# Adafruit_SMT_Datalogger_Shield.net
KiCad netlist of a schematic drawn in EAGLE
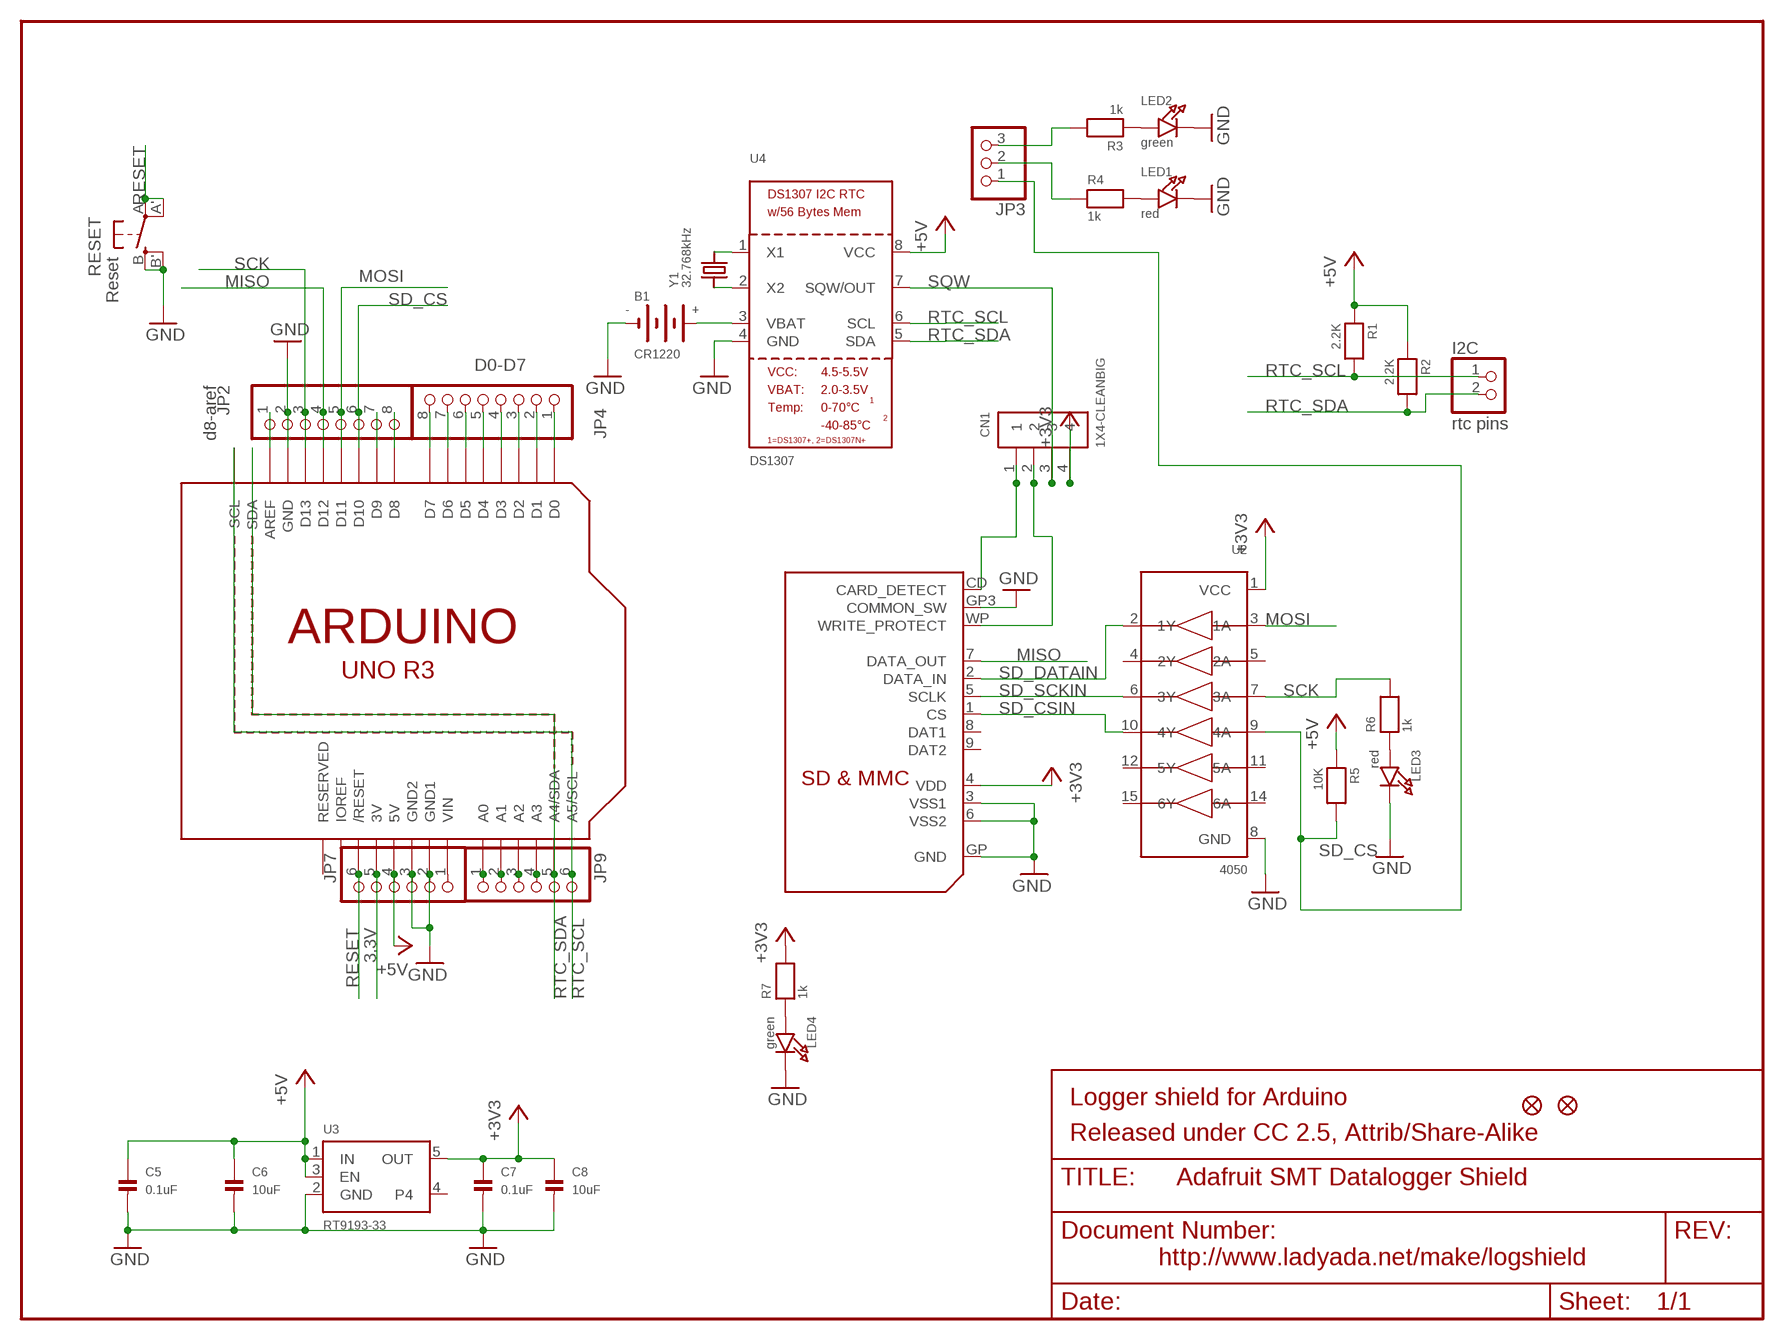
[diagram p0: schematic, sheet 1]

(export (version "E")
  (design (tool "Eeschema 10.0.6"))
  (components
    (comp (ref "B1")
      (value "CR1220")
      (footprint "eagle-import:CR1220")
      (libsource (lib "eagle-import") (part "BATTERYCR1220_SMT"))
    )
    (comp (ref "C5")
      (value "0.1uF")
      (footprint "eagle-import:0805")
      (libsource (lib "eagle-import") (part "CAP_CERAMIC0805"))
    )
    (comp (ref "C6")
      (value "10uF")
      (footprint "eagle-import:0805")
      (libsource (lib "eagle-import") (part "CAP_CERAMIC0805"))
    )
    (comp (ref "C7")
      (value "0.1uF")
      (footprint "eagle-import:0805")
      (libsource (lib "eagle-import") (part "CAP_CERAMIC0805"))
    )
    (comp (ref "C8")
      (value "10uF")
      (footprint "eagle-import:0805")
      (libsource (lib "eagle-import") (part "CAP_CERAMIC0805"))
    )
    (comp (ref "CN1")
      (value "1X4-CLEANBIG")
      (footprint "eagle-import:1X04-CLEANBIG")
      (libsource (lib "eagle-import") (part "1X4-CLEANBIG"))
    )
    (comp (ref "FID1")
      (value "FIDUCIAL1X2.5")
      (footprint "eagle-import:FIDUCIAL-1X2.5")
      (libsource (lib "eagle-import") (part "FIDUCIAL1X2.5"))
    )
    (comp (ref "FID3")
      (value "FIDUCIAL1X2.5")
      (footprint "eagle-import:FIDUCIAL-1X2.5")
      (libsource (lib "eagle-import") (part "FIDUCIAL1X2.5"))
    )
    (comp (ref "I2C")
      (value "rtc pins")
      (footprint "eagle-import:1X02")
      (libsource (lib "eagle-import") (part "PINHD-1X2"))
    )
    (comp (ref "JP2")
      (value "d8-aref")
      (footprint "eagle-import:1X08-BIG")
      (libsource (lib "eagle-import") (part "PINHD-1X8BIG"))
    )
    (comp (ref "JP3")
      (value "HEADER-1X3ROUND")
      (footprint "eagle-import:1X03_ROUND")
      (libsource (lib "eagle-import") (part "HEADER-1X3ROUND"))
    )
    (comp (ref "JP4")
      (value "D0-D7")
      (footprint "eagle-import:1X08-BIG")
      (libsource (lib "eagle-import") (part "PINHD-1X8BIG"))
    )
    (comp (ref "JP7")
      (value "PINHD-1X6B")
      (footprint "eagle-import:1X06-BIG")
      (libsource (lib "eagle-import") (part "PINHD-1X6B"))
    )
    (comp (ref "JP9")
      (value "PINHD-1X6B")
      (footprint "eagle-import:1X06-BIG")
      (libsource (lib "eagle-import") (part "PINHD-1X6B"))
    )
    (comp (ref "LED1")
      (value "red")
      (footprint "eagle-import:CHIPLED_0805")
      (libsource (lib "eagle-import") (part "LED0805"))
    )
    (comp (ref "LED2")
      (value "green")
      (footprint "eagle-import:CHIPLED_0805")
      (libsource (lib "eagle-import") (part "LED0805"))
    )
    (comp (ref "LED3")
      (value "red")
      (footprint "eagle-import:CHIPLED_0805")
      (libsource (lib "eagle-import") (part "LED0805"))
    )
    (comp (ref "LED4")
      (value "green")
      (footprint "eagle-import:CHIPLED_0805")
      (libsource (lib "eagle-import") (part "LED0805"))
    )
    (comp (ref "R1")
      (value "2.2K")
      (footprint "eagle-import:0805")
      (libsource (lib "eagle-import") (part "RESISTOR0805"))
    )
    (comp (ref "R2")
      (value "2.2K")
      (footprint "eagle-import:0805")
      (libsource (lib "eagle-import") (part "RESISTOR0805"))
    )
    (comp (ref "R3")
      (value "1k")
      (footprint "eagle-import:0805")
      (libsource (lib "eagle-import") (part "RESISTOR0805"))
    )
    (comp (ref "R4")
      (value "1k")
      (footprint "eagle-import:0805")
      (libsource (lib "eagle-import") (part "RESISTOR0805"))
    )
    (comp (ref "R5")
      (value "10K")
      (footprint "eagle-import:0805")
      (libsource (lib "eagle-import") (part "RESISTOR0805"))
    )
    (comp (ref "R6")
      (value "1k")
      (footprint "eagle-import:0805")
      (libsource (lib "eagle-import") (part "RESISTOR0805"))
    )
    (comp (ref "R7")
      (value "1k")
      (footprint "eagle-import:0805")
      (libsource (lib "eagle-import") (part "RESISTOR0805"))
    )
    (comp (ref "RESET")
      (value "Reset")
      (footprint "eagle-import:EVQ-Q2")
      (libsource (lib "eagle-import") (part "SPST_TACT-EVQQ2"))
    )
    (comp (ref "U$2")
      (value "SDMMC06132")
      (footprint "eagle-import:06132")
      (libsource (lib "eagle-import") (part "SDMMC06132"))
    )
    (comp (ref "U1")
      (value "ARDUINOR3-DIMENSION")
      (footprint "eagle-import:ARDUINOR3")
      (libsource (lib "eagle-import") (part "ARDUINOR3-DIMENSION"))
    )
    (comp (ref "U2")
      (value "4050")
      (footprint "eagle-import:SOIC16")
      (libsource (lib "eagle-import") (part "74HC4050D"))
    )
    (comp (ref "U3")
      (value "RT9193-33")
      (footprint "eagle-import:SOT23-5")
      (libsource (lib "eagle-import") (part "VREG_SOT23-5"))
    )
    (comp (ref "U4")
      (value "DS1307")
      (footprint "eagle-import:SOIC8_150MIL")
      (libsource (lib "eagle-import") (part "RTC_DS1307"))
    )
    (comp (ref "Y1")
      (value "32.768kHz")
      (footprint "eagle-import:CRYSTAL_8X3.8")
      (libsource (lib "eagle-import") (part "CRYSTAL8X3.8SMT"))
    )
  )
  (nets
    (net (code "1") (name "+3V3") (class "Default")
      (node (ref "C7") (pin "1") (pinfunction "P$1_1") (pintype "passive"))
      (node (ref "C8") (pin "1") (pinfunction "P$1_1") (pintype "passive"))
      (node (ref "CN1") (pin "4") (pinfunction "4_4") (pintype "bidirectional"))
      (node (ref "R7") (pin "2") (pinfunction "2_2") (pintype "passive"))
      (node (ref "U$2") (pin "4") (pinfunction "VDD_4") (pintype "power_in"))
      (node (ref "U2") (pin "1") (pinfunction "VCC_1") (pintype "bidirectional"))
      (node (ref "U3") (pin "5") (pinfunction "OUT_5") (pintype "bidirectional"))
    )
    (net (code "2") (name "+5V") (class "Default")
      (node (ref "C5") (pin "1") (pinfunction "P$1_1") (pintype "passive"))
      (node (ref "C6") (pin "1") (pinfunction "P$1_1") (pintype "passive"))
      (node (ref "JP7") (pin "4") (pinfunction "4_4") (pintype "passive"))
      (node (ref "R1") (pin "1") (pinfunction "1_1") (pintype "passive"))
      (node (ref "R2") (pin "1") (pinfunction "1_1") (pintype "passive"))
      (node (ref "R5") (pin "1") (pinfunction "1_1") (pintype "passive"))
      (node (ref "U1") (pin "5V") (pinfunction "5V_5V") (pintype "power_in"))
      (node (ref "U3") (pin "1") (pinfunction "IN_1") (pintype "bidirectional"))
      (node (ref "U3") (pin "3") (pinfunction "EN_3") (pintype "bidirectional"))
      (node (ref "U4") (pin "8") (pinfunction "VCC_8") (pintype "bidirectional"))
    )
    (net (code "3") (name "/3.3V") (class "Default")
      (node (ref "JP7") (pin "5") (pinfunction "5_5") (pintype "passive"))
      (node (ref "U1") (pin "3V") (pinfunction "3V_3V") (pintype "power_in"))
    )
    (net (code "4") (name "/MISO") (class "Default")
      (node (ref "JP2") (pin "4") (pinfunction "4_4") (pintype "passive"))
      (node (ref "U$2") (pin "7") (pinfunction "DATA_OUT_7") (pintype "output"))
      (node (ref "U1") (pin "D12") (pinfunction "D12_D12") (pintype "bidirectional"))
    )
    (net (code "5") (name "/MOSI") (class "Default")
      (node (ref "JP2") (pin "5") (pinfunction "5_5") (pintype "passive"))
      (node (ref "U1") (pin "D11") (pinfunction "D11_D11") (pintype "bidirectional"))
      (node (ref "U2") (pin "3") (pinfunction "1A_3") (pintype "bidirectional"))
    )
    (net (code "6") (name "/RESET") (class "Default")
      (node (ref "JP7") (pin "6") (pinfunction "6_6") (pintype "passive"))
      (node (ref "RESET") (pin "A") (pinfunction "P_A") (pintype "passive"))
      (node (ref "RESET") (pin "A'") (pinfunction "P1_A'") (pintype "passive"))
      (node (ref "U1") (pin "RESET") (pinfunction "/RESET_RESET") (pintype "bidirectional"))
    )
    (net (code "7") (name "/RTC_SCL") (class "Default")
      (node (ref "I2C") (pin "1") (pinfunction "1_1") (pintype "passive"))
      (node (ref "JP9") (pin "6") (pinfunction "6_6") (pintype "passive"))
      (node (ref "R1") (pin "2") (pinfunction "2_2") (pintype "passive"))
      (node (ref "U1") (pin "A5") (pinfunction "A5/SCL_A5") (pintype "bidirectional"))
      (node (ref "U1") (pin "SCL") (pinfunction "SCL_SCL") (pintype "bidirectional"))
      (node (ref "U4") (pin "6") (pinfunction "SCL_6") (pintype "bidirectional"))
    )
    (net (code "8") (name "/RTC_SDA") (class "Default")
      (node (ref "I2C") (pin "2") (pinfunction "2_2") (pintype "passive"))
      (node (ref "JP9") (pin "5") (pinfunction "5_5") (pintype "passive"))
      (node (ref "R2") (pin "2") (pinfunction "2_2") (pintype "passive"))
      (node (ref "U1") (pin "A4") (pinfunction "A4/SDA_A4") (pintype "bidirectional"))
      (node (ref "U1") (pin "SDA") (pinfunction "SDA_SDA") (pintype "bidirectional"))
      (node (ref "U4") (pin "5") (pinfunction "SDA_5") (pintype "bidirectional"))
    )
    (net (code "9") (name "/SCK") (class "Default")
      (node (ref "JP2") (pin "3") (pinfunction "3_3") (pintype "passive"))
      (node (ref "R6") (pin "2") (pinfunction "2_2") (pintype "passive"))
      (node (ref "U1") (pin "D13") (pinfunction "D13_D13") (pintype "bidirectional"))
      (node (ref "U2") (pin "7") (pinfunction "3A_7") (pintype "bidirectional"))
    )
    (net (code "10") (name "/SD_CS") (class "Default")
      (node (ref "JP2") (pin "6") (pinfunction "6_6") (pintype "passive"))
      (node (ref "JP3") (pin "1") (pinfunction "1_1") (pintype "passive"))
      (node (ref "R5") (pin "2") (pinfunction "2_2") (pintype "passive"))
      (node (ref "U1") (pin "D10") (pinfunction "D10_D10") (pintype "bidirectional"))
      (node (ref "U2") (pin "9") (pinfunction "4A_9") (pintype "bidirectional"))
    )
    (net (code "11") (name "/SD_CSIN") (class "Default")
      (node (ref "U$2") (pin "1") (pinfunction "CS_1") (pintype "input"))
      (node (ref "U2") (pin "10") (pinfunction "4Y_10") (pintype "bidirectional"))
    )
    (net (code "12") (name "/SD_DATAIN") (class "Default")
      (node (ref "U$2") (pin "2") (pinfunction "DATA_IN_2") (pintype "input"))
      (node (ref "U2") (pin "2") (pinfunction "1Y_2") (pintype "bidirectional"))
    )
    (net (code "13") (name "/SD_SCKIN") (class "Default")
      (node (ref "U$2") (pin "5") (pinfunction "SCLK_5") (pintype "input"))
      (node (ref "U2") (pin "6") (pinfunction "3Y_6") (pintype "bidirectional"))
    )
    (net (code "14") (name "/SQW") (class "Default")
      (node (ref "CN1") (pin "3") (pinfunction "3_3") (pintype "bidirectional"))
      (node (ref "U4") (pin "7") (pinfunction "SQW/OUT_7") (pintype "bidirectional"))
    )
    (net (code "15") (name "GND") (class "Default")
      (node (ref "B1") (pin "-") (pinfunction "-_-") (pintype "passive"))
      (node (ref "C5") (pin "2") (pinfunction "P$2_2") (pintype "passive"))
      (node (ref "C6") (pin "2") (pinfunction "P$2_2") (pintype "passive"))
      (node (ref "C7") (pin "2") (pinfunction "P$2_2") (pintype "passive"))
      (node (ref "C8") (pin "2") (pinfunction "P$2_2") (pintype "passive"))
      (node (ref "JP2") (pin "2") (pinfunction "2_2") (pintype "passive"))
      (node (ref "JP7") (pin "2") (pinfunction "2_2") (pintype "passive"))
      (node (ref "JP7") (pin "3") (pinfunction "3_3") (pintype "passive"))
      (node (ref "LED1") (pin "C") (pinfunction "C_C") (pintype "passive"))
      (node (ref "LED2") (pin "C") (pinfunction "C_C") (pintype "passive"))
      (node (ref "LED3") (pin "C") (pinfunction "C_C") (pintype "passive"))
      (node (ref "LED4") (pin "C") (pinfunction "C_C") (pintype "passive"))
      (node (ref "RESET") (pin "B") (pinfunction "S_B") (pintype "passive"))
      (node (ref "RESET") (pin "B'") (pinfunction "S1_B'") (pintype "passive"))
      (node (ref "U$2") (pin "3") (pinfunction "VSS1_3") (pintype "power_in"))
      (node (ref "U$2") (pin "6") (pinfunction "VSS2_6") (pintype "power_in"))
      (node (ref "U$2") (pin "GP") (pinfunction "GND_GP") (pintype "power_in"))
      (node (ref "U$2") (pin "GP3") (pinfunction "COMMON_SW_GP3") (pintype "passive"))
      (node (ref "U1") (pin "GND") (pinfunction "GND_GND") (pintype "power_in"))
      (node (ref "U1") (pin "GND1") (pinfunction "GND1_GND1") (pintype "power_in"))
      (node (ref "U1") (pin "GND2") (pinfunction "GND2_GND2") (pintype "power_in"))
      (node (ref "U2") (pin "8") (pinfunction "GND_8") (pintype "bidirectional"))
      (node (ref "U3") (pin "2") (pinfunction "GND_2") (pintype "bidirectional"))
      (node (ref "U4") (pin "4") (pinfunction "GND_4") (pintype "bidirectional"))
    )
    (net (code "16") (name "Net-(B1-+)") (class "Default")
      (node (ref "B1") (pin "+$1") (pinfunction "+_+$1") (pintype "passive"))
      (node (ref "U4") (pin "3") (pinfunction "VBAT_3") (pintype "bidirectional"))
    )
    (net (code "17") (name "Net-(JP2-Pad1)") (class "Default")
      (node (ref "JP2") (pin "1") (pinfunction "1_1") (pintype "passive"))
      (node (ref "U1") (pin "AREF") (pinfunction "AREF_AREF") (pintype "bidirectional"))
    )
    (net (code "18") (name "Net-(JP2-Pad7)") (class "Default")
      (node (ref "JP2") (pin "7") (pinfunction "7_7") (pintype "passive"))
      (node (ref "U1") (pin "D9") (pinfunction "D9_D9") (pintype "bidirectional"))
    )
    (net (code "19") (name "Net-(JP2-Pad8)") (class "Default")
      (node (ref "JP2") (pin "8") (pinfunction "8_8") (pintype "passive"))
      (node (ref "U1") (pin "D8") (pinfunction "D8_D8") (pintype "bidirectional"))
    )
    (net (code "20") (name "Net-(JP3-Pad2)") (class "Default")
      (node (ref "JP3") (pin "2") (pinfunction "2_2") (pintype "passive"))
      (node (ref "R4") (pin "1") (pinfunction "1_1") (pintype "passive"))
    )
    (net (code "21") (name "Net-(JP3-Pad3)") (class "Default")
      (node (ref "JP3") (pin "3") (pinfunction "3_3") (pintype "passive"))
      (node (ref "R3") (pin "2") (pinfunction "2_2") (pintype "passive"))
    )
    (net (code "22") (name "Net-(JP4-Pad1)") (class "Default")
      (node (ref "JP4") (pin "1") (pinfunction "1_1") (pintype "passive"))
      (node (ref "U1") (pin "D0") (pinfunction "D0_D0") (pintype "bidirectional"))
    )
    (net (code "23") (name "Net-(JP4-Pad2)") (class "Default")
      (node (ref "JP4") (pin "2") (pinfunction "2_2") (pintype "passive"))
      (node (ref "U1") (pin "D1") (pinfunction "D1_D1") (pintype "bidirectional"))
    )
    (net (code "24") (name "Net-(JP4-Pad3)") (class "Default")
      (node (ref "JP4") (pin "3") (pinfunction "3_3") (pintype "passive"))
      (node (ref "U1") (pin "D2") (pinfunction "D2_D2") (pintype "bidirectional"))
    )
    (net (code "25") (name "Net-(JP4-Pad4)") (class "Default")
      (node (ref "JP4") (pin "4") (pinfunction "4_4") (pintype "passive"))
      (node (ref "U1") (pin "D3") (pinfunction "D3_D3") (pintype "bidirectional"))
    )
    (net (code "26") (name "Net-(JP4-Pad5)") (class "Default")
      (node (ref "JP4") (pin "5") (pinfunction "5_5") (pintype "passive"))
      (node (ref "U1") (pin "D4") (pinfunction "D4_D4") (pintype "bidirectional"))
    )
    (net (code "27") (name "Net-(JP4-Pad6)") (class "Default")
      (node (ref "JP4") (pin "6") (pinfunction "6_6") (pintype "passive"))
      (node (ref "U1") (pin "D5") (pinfunction "D5_D5") (pintype "bidirectional"))
    )
    (net (code "28") (name "Net-(JP4-Pad7)") (class "Default")
      (node (ref "JP4") (pin "7") (pinfunction "7_7") (pintype "passive"))
      (node (ref "U1") (pin "D6") (pinfunction "D6_D6") (pintype "bidirectional"))
    )
    (net (code "29") (name "Net-(JP4-Pad8)") (class "Default")
      (node (ref "JP4") (pin "8") (pinfunction "8_8") (pintype "passive"))
      (node (ref "U1") (pin "D7") (pinfunction "D7_D7") (pintype "bidirectional"))
    )
    (net (code "30") (name "Net-(JP7-Pad1)") (class "Default")
      (node (ref "JP7") (pin "1") (pinfunction "1_1") (pintype "passive"))
      (node (ref "U1") (pin "VIN") (pinfunction "VIN_VIN") (pintype "power_in"))
    )
    (net (code "31") (name "Net-(JP9-Pad1)") (class "Default")
      (node (ref "JP9") (pin "1") (pinfunction "1_1") (pintype "passive"))
      (node (ref "U1") (pin "A0") (pinfunction "A0_A0") (pintype "bidirectional"))
    )
    (net (code "32") (name "Net-(JP9-Pad2)") (class "Default")
      (node (ref "JP9") (pin "2") (pinfunction "2_2") (pintype "passive"))
      (node (ref "U1") (pin "A1") (pinfunction "A1_A1") (pintype "bidirectional"))
    )
    (net (code "33") (name "Net-(JP9-Pad3)") (class "Default")
      (node (ref "JP9") (pin "3") (pinfunction "3_3") (pintype "passive"))
      (node (ref "U1") (pin "A2") (pinfunction "A2_A2") (pintype "bidirectional"))
    )
    (net (code "34") (name "Net-(JP9-Pad4)") (class "Default")
      (node (ref "JP9") (pin "4") (pinfunction "4_4") (pintype "passive"))
      (node (ref "U1") (pin "A3") (pinfunction "A3_A3") (pintype "bidirectional"))
    )
    (net (code "35") (name "Net-(LED1-PadA)") (class "Default")
      (node (ref "LED1") (pin "A") (pinfunction "A_A") (pintype "passive"))
      (node (ref "R4") (pin "2") (pinfunction "2_2") (pintype "passive"))
    )
    (net (code "36") (name "Net-(LED2-PadA)") (class "Default")
      (node (ref "LED2") (pin "A") (pinfunction "A_A") (pintype "passive"))
      (node (ref "R3") (pin "1") (pinfunction "1_1") (pintype "passive"))
    )
    (net (code "37") (name "Net-(LED3-PadA)") (class "Default")
      (node (ref "LED3") (pin "A") (pinfunction "A_A") (pintype "passive"))
      (node (ref "R6") (pin "1") (pinfunction "1_1") (pintype "passive"))
    )
    (net (code "38") (name "Net-(LED4-PadA)") (class "Default")
      (node (ref "LED4") (pin "A") (pinfunction "A_A") (pintype "passive"))
      (node (ref "R7") (pin "1") (pinfunction "1_1") (pintype "passive"))
    )
    (net (code "39") (name "Net-(U$2-CARD_DETECT)") (class "Default")
      (node (ref "CN1") (pin "1") (pinfunction "1_1") (pintype "bidirectional"))
      (node (ref "U$2") (pin "CD") (pinfunction "CARD_DETECT_CD") (pintype "passive"))
    )
    (net (code "40") (name "Net-(U$2-WRITE_PROTECT)") (class "Default")
      (node (ref "CN1") (pin "2") (pinfunction "2_2") (pintype "bidirectional"))
      (node (ref "U$2") (pin "WP") (pinfunction "WRITE_PROTECT_WP") (pintype "passive"))
    )
    (net (code "41") (name "Net-(U4-X1)") (class "Default")
      (node (ref "U4") (pin "1") (pinfunction "X1_1") (pintype "bidirectional"))
      (node (ref "Y1") (pin "P$4") (pinfunction "2_P$4") (pintype "passive"))
    )
    (net (code "42") (name "Net-(U4-X2)") (class "Default")
      (node (ref "U4") (pin "2") (pinfunction "X2_2") (pintype "bidirectional"))
      (node (ref "Y1") (pin "P$1") (pinfunction "1_P$1") (pintype "passive"))
    )
    (net (code "43") (name "unconnected-(U$2-DAT1-Pad8)") (class "Default")
      (node (ref "U$2") (pin "8") (pinfunction "DAT1_8") (pintype "bidirectional"))
    )
    (net (code "44") (name "unconnected-(U$2-DAT2-Pad9)") (class "Default")
      (node (ref "U$2") (pin "9") (pinfunction "DAT2_9") (pintype "bidirectional"))
    )
    (net (code "45") (name "unconnected-(U1-PadIOREF)") (class "Default")
      (node (ref "U1") (pin "IOREF") (pinfunction "IOREF_IOREF") (pintype "output"))
    )
    (net (code "46") (name "unconnected-(U1-PadRESERVED)") (class "Default")
      (node (ref "U1") (pin "RESERVED") (pinfunction "RESERVED_RESERVED") (pintype "no_connect"))
    )
    (net (code "47") (name "unconnected-(U2-2A-Pad5)") (class "Default")
      (node (ref "U2") (pin "5") (pinfunction "2A_5") (pintype "bidirectional"))
    )
    (net (code "48") (name "unconnected-(U2-2Y-Pad4)") (class "Default")
      (node (ref "U2") (pin "4") (pinfunction "2Y_4") (pintype "bidirectional"))
    )
    (net (code "49") (name "unconnected-(U2-5A-Pad11)") (class "Default")
      (node (ref "U2") (pin "11") (pinfunction "5A_11") (pintype "bidirectional"))
    )
    (net (code "50") (name "unconnected-(U2-5Y-Pad12)") (class "Default")
      (node (ref "U2") (pin "12") (pinfunction "5Y_12") (pintype "bidirectional"))
    )
    (net (code "51") (name "unconnected-(U2-6A-Pad14)") (class "Default")
      (node (ref "U2") (pin "14") (pinfunction "6A_14") (pintype "bidirectional"))
    )
    (net (code "52") (name "unconnected-(U2-6Y-Pad15)") (class "Default")
      (node (ref "U2") (pin "15") (pinfunction "6Y_15") (pintype "bidirectional"))
    )
    (net (code "53") (name "unconnected-(U3-P4-Pad4)") (class "Default")
      (node (ref "U3") (pin "4") (pinfunction "P4_4") (pintype "bidirectional"))
    )
  )
)
